# MIDI_Synthesizer.net
KiCad netlist of a schematic drawn in Altium Designer
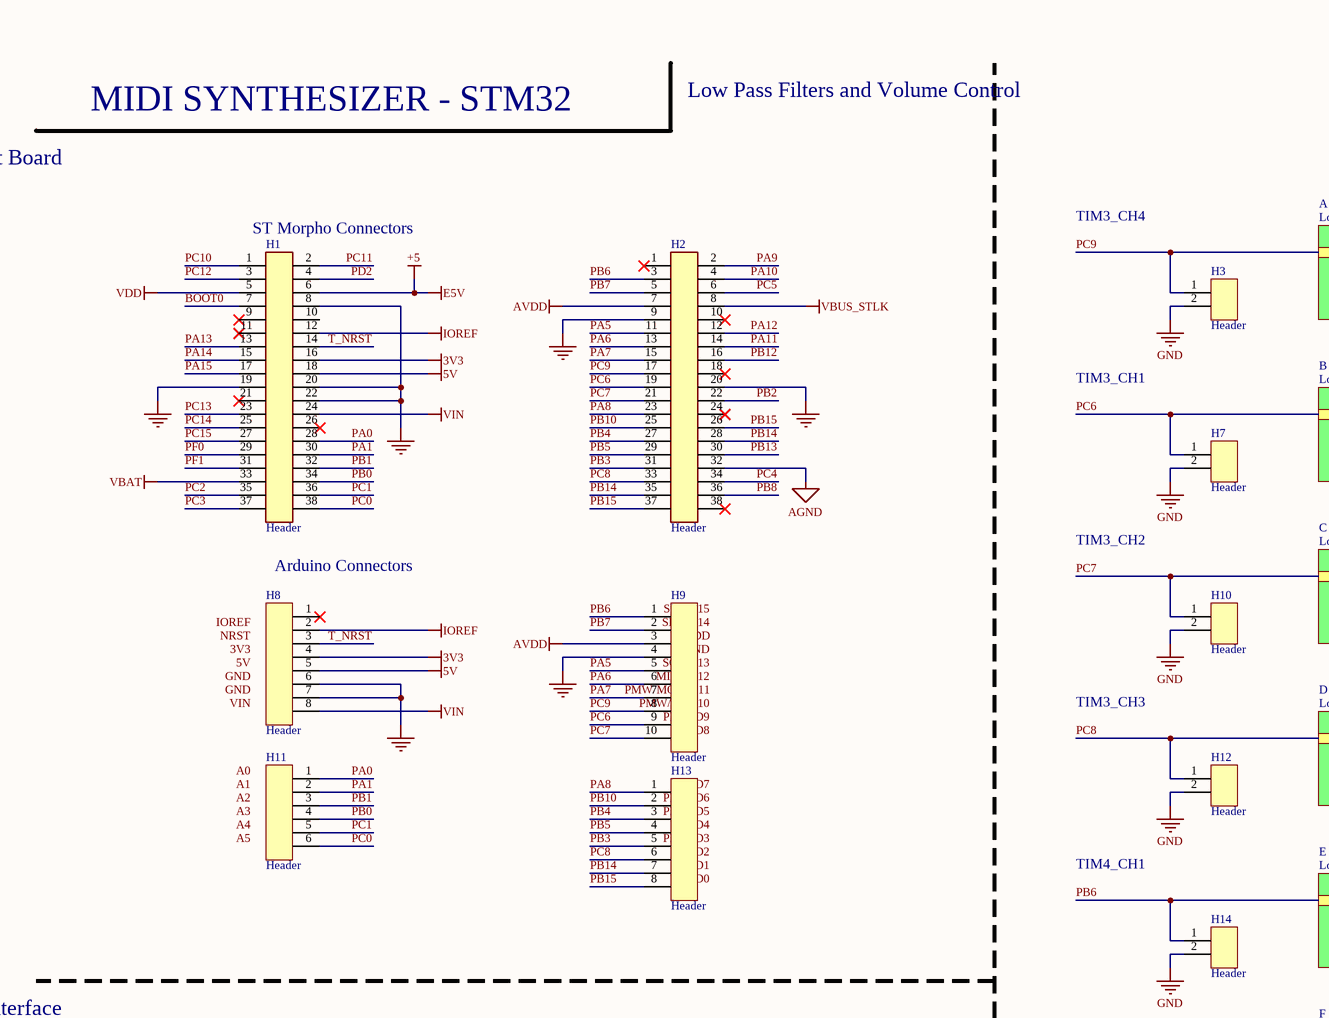
[diagram p0: MIDI_Synthesizer.SchDoc, top left]
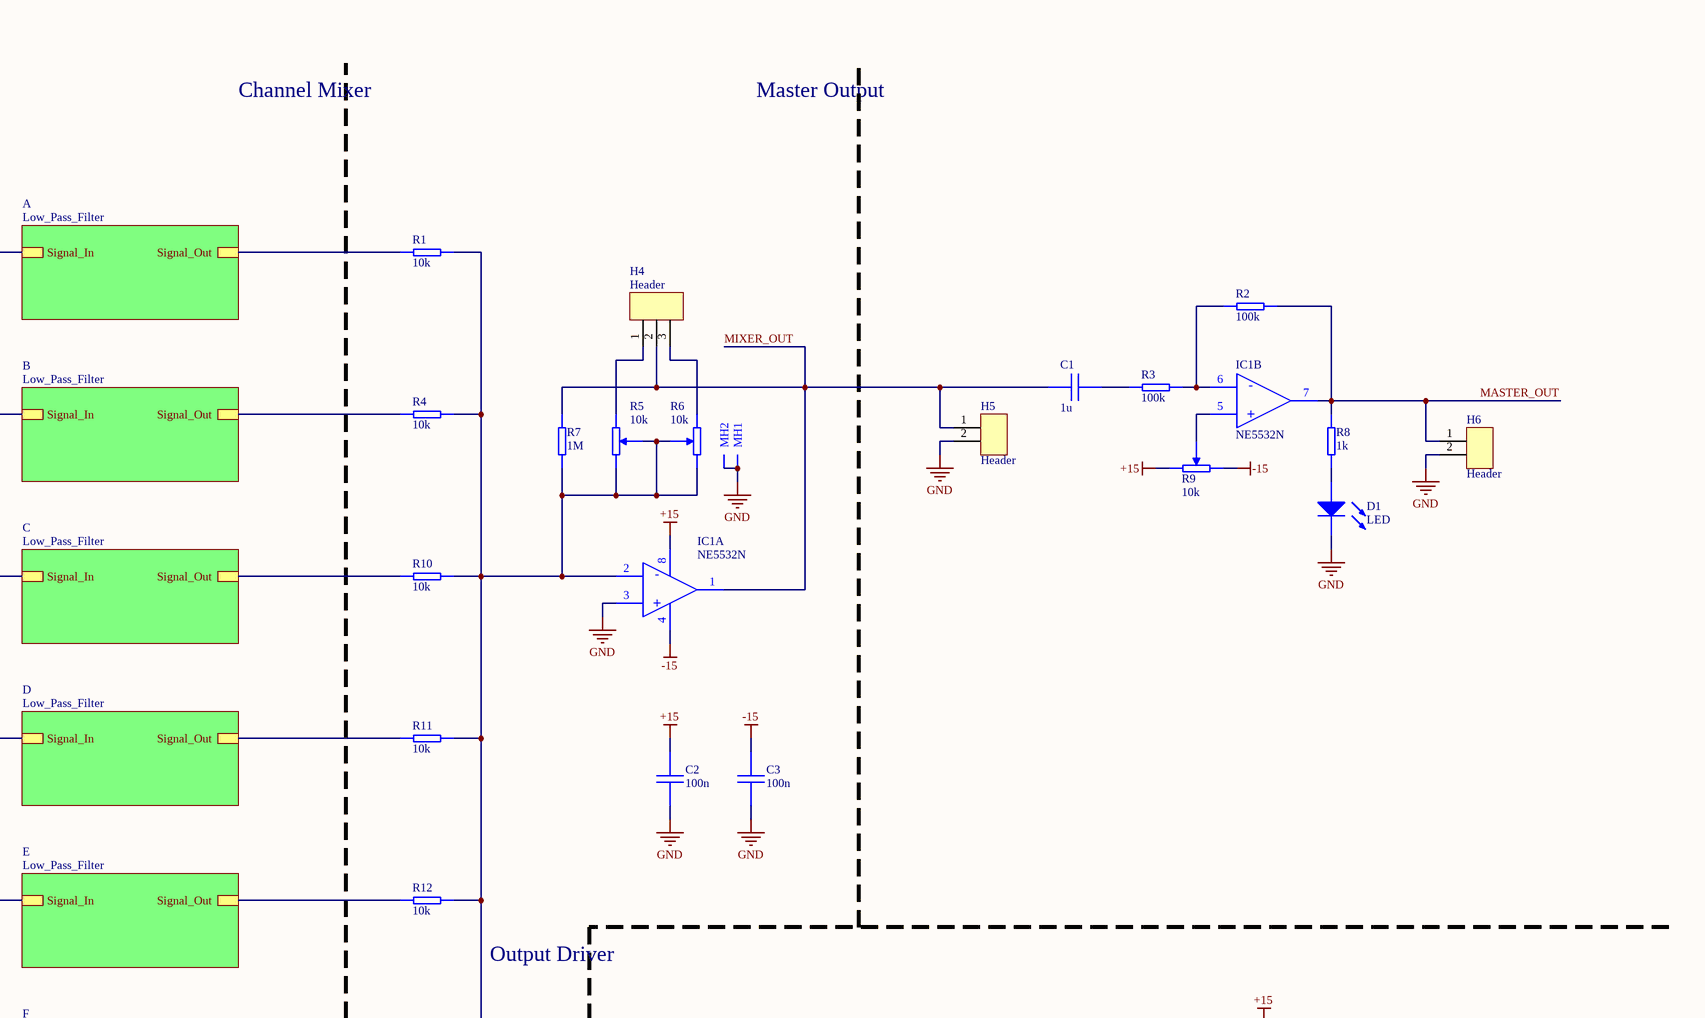
[diagram p1: MIDI_Synthesizer.SchDoc, top right]
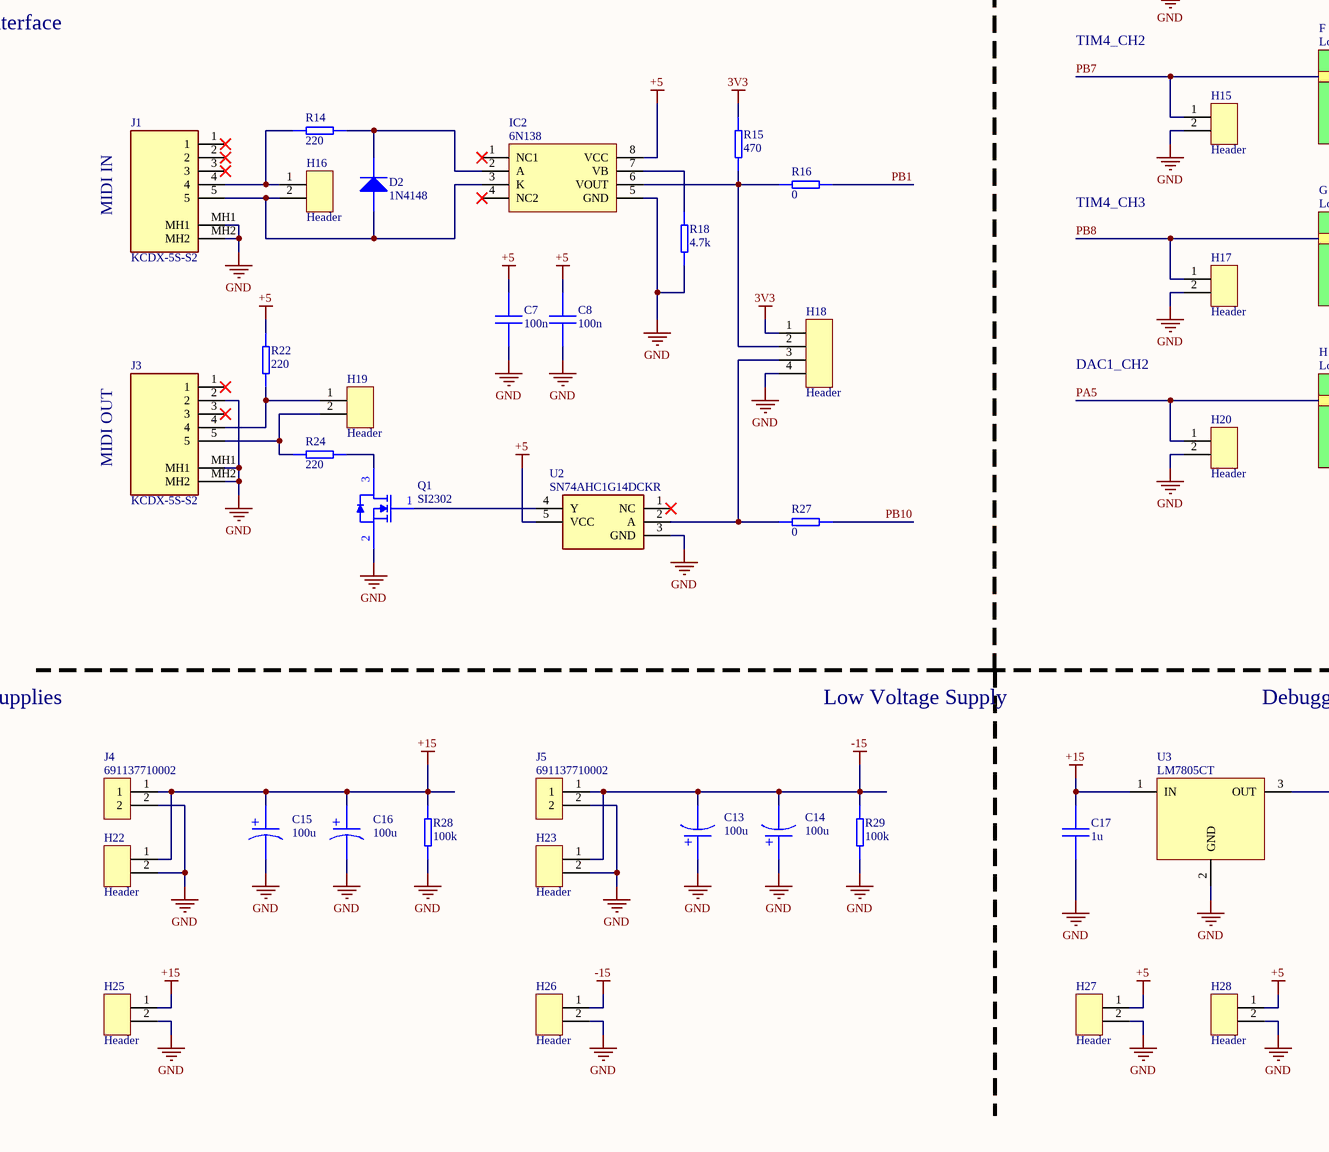
[diagram p2: MIDI_Synthesizer.SchDoc, bottom left]
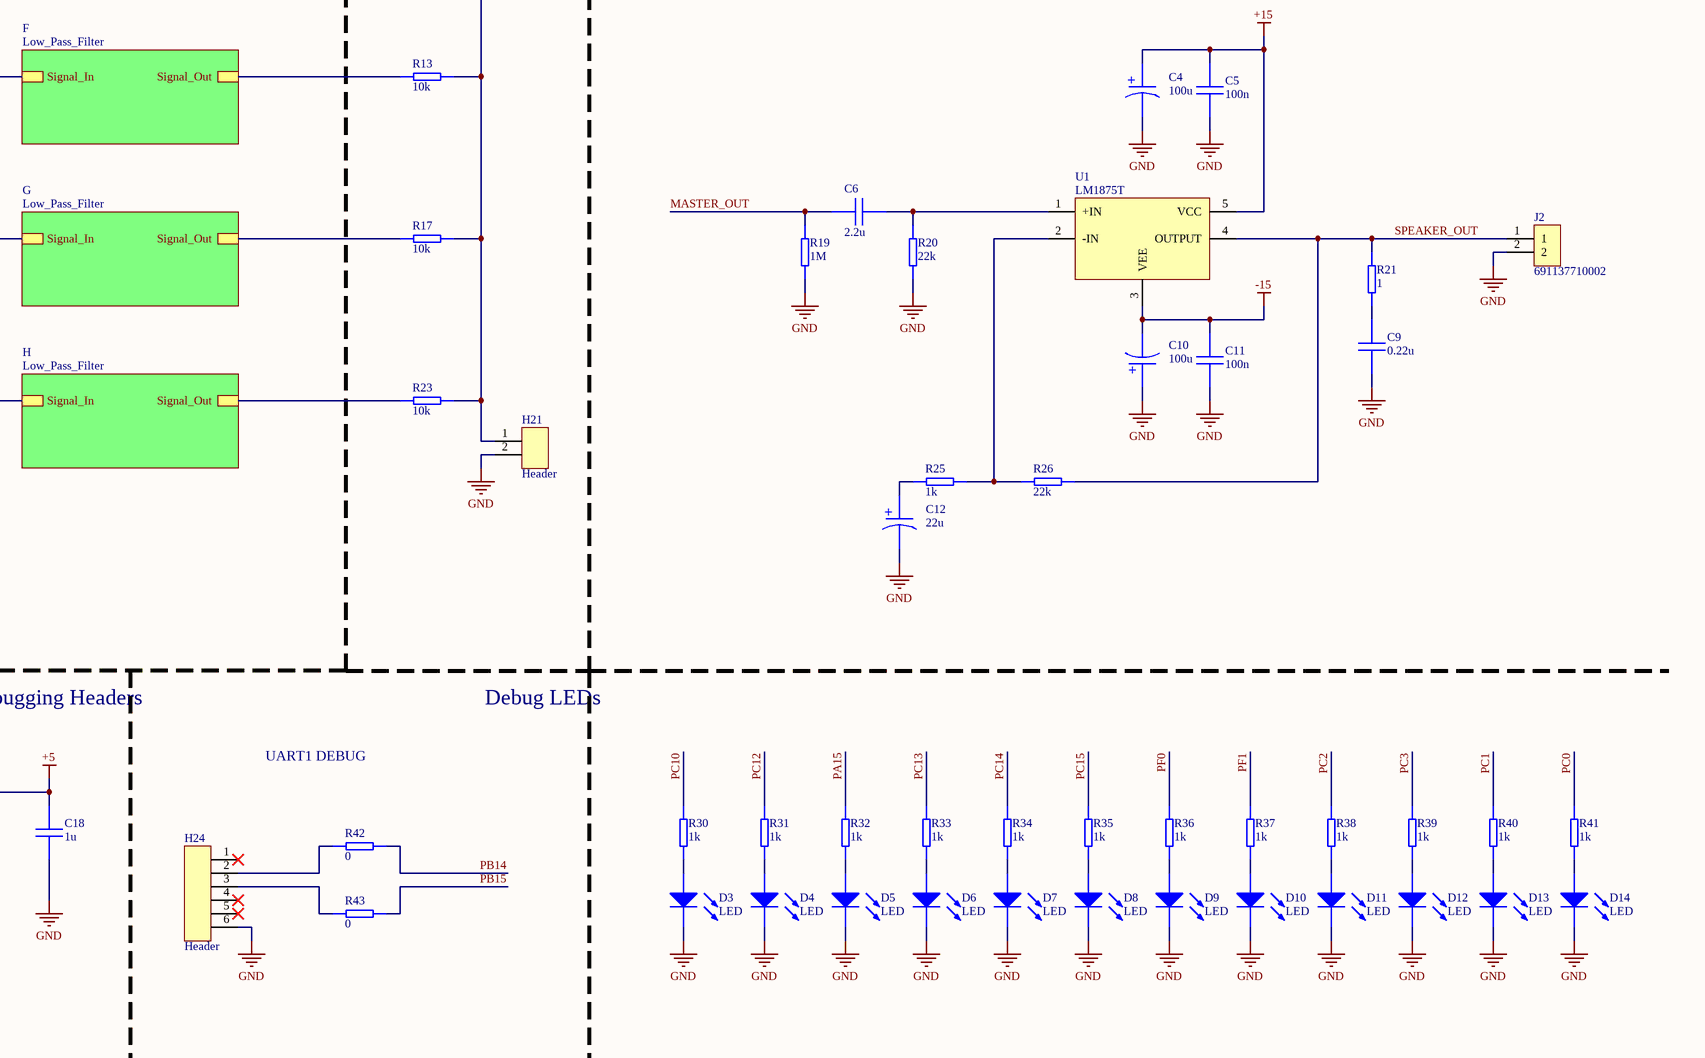
[diagram p3: MIDI_Synthesizer.SchDoc, bottom right]

(export (version "E")
  (design (tool "Eeschema 10.0.6"))
  (components
    (comp (ref "C1")
      (value "1u")
      (footprint "CAP0805")
      (description "Non Polarized Capacitor")
      (libsource (lib "TD") (part "Capacitor - Non Polarized"))
    )
    (comp (ref "C2")
      (value "100n")
      (footprint "CAP0805")
      (description "Non Polarized Capacitor")
      (libsource (lib "TD") (part "Capacitor - Non Polarized"))
    )
    (comp (ref "C3")
      (value "100n")
      (footprint "CAP0805")
      (description "Non Polarized Capacitor")
      (libsource (lib "TD") (part "Capacitor - Non Polarized"))
    )
    (comp (ref "C4")
      (value "100u")
      (footprint "CAPSMD660X800N")
      (description "Polarized Capacitor")
      (libsource (lib "TD") (part "Capacitor - Polarized"))
    )
    (comp (ref "C5")
      (value "100n")
      (footprint "CAP0805")
      (description "Non Polarized Capacitor")
      (libsource (lib "TD") (part "Capacitor - Non Polarized"))
    )
    (comp (ref "C6")
      (value "2.2u")
      (footprint "CAP0805")
      (description "Non Polarized Capacitor")
      (libsource (lib "TD") (part "Capacitor - Non Polarized"))
    )
    (comp (ref "C7")
      (value "100n")
      (footprint "CAP0805")
      (description "Non Polarized Capacitor")
      (libsource (lib "TD") (part "Capacitor - Non Polarized"))
    )
    (comp (ref "C8")
      (value "100n")
      (footprint "CAP0805")
      (description "Non Polarized Capacitor")
      (libsource (lib "TD") (part "Capacitor - Non Polarized"))
    )
    (comp (ref "C9")
      (value "0.22u")
      (footprint "CAP0805")
      (description "Non Polarized Capacitor")
      (libsource (lib "TD") (part "Capacitor - Non Polarized"))
    )
    (comp (ref "C10")
      (value "100u")
      (footprint "CAPSMD660X800N")
      (description "Polarized Capacitor")
      (libsource (lib "") (part "Capacitor - Polarized_1"))
    )
    (comp (ref "C11")
      (value "100n")
      (footprint "CAP0805")
      (description "Non Polarized Capacitor")
      (libsource (lib "TD") (part "Capacitor - Non Polarized"))
    )
    (comp (ref "C12")
      (value "22u")
      (footprint "CAPSMD530X550N")
      (description "Polarized Capacitor")
      (libsource (lib "TD") (part "Capacitor - Polarized"))
    )
    (comp (ref "C13")
      (value "100u")
      (footprint "CAPSMD660X800N")
      (description "Polarized Capacitor")
      (libsource (lib "") (part "Capacitor - Polarized_1"))
    )
    (comp (ref "C14")
      (value "100u")
      (footprint "CAPSMD660X800N")
      (description "Polarized Capacitor")
      (libsource (lib "") (part "Capacitor - Polarized_1"))
    )
    (comp (ref "C15")
      (value "100u")
      (footprint "CAPSMD660X800N")
      (description "Polarized Capacitor")
      (libsource (lib "TD") (part "Capacitor - Polarized"))
    )
    (comp (ref "C16")
      (value "100u")
      (footprint "CAPSMD660X800N")
      (description "Polarized Capacitor")
      (libsource (lib "TD") (part "Capacitor - Polarized"))
    )
    (comp (ref "C17")
      (value "1u")
      (footprint "CAP0805")
      (description "Non Polarized Capacitor")
      (libsource (lib "TD") (part "Capacitor - Non Polarized"))
    )
    (comp (ref "C18")
      (value "1u")
      (footprint "CAP0805")
      (description "Non Polarized Capacitor")
      (libsource (lib "TD") (part "Capacitor - Non Polarized"))
    )
    (comp (ref "D1")
      (value "LED")
      (footprint "LEDM1608X90N")
      (description "General Purpose LED")
      (libsource (lib "TD") (part "LED"))
    )
    (comp (ref "D2")
      (value "1N4148")
      (footprint "SOD123")
      (description "1N4148 General Purpose Switching Diode")
      (libsource (lib "TD") (part "1N4148"))
    )
    (comp (ref "D3")
      (value "LED")
      (footprint "LEDM1608X90N")
      (description "General Purpose LED")
      (libsource (lib "TD") (part "LED"))
    )
    (comp (ref "D4")
      (value "LED")
      (footprint "LEDM1608X90N")
      (description "General Purpose LED")
      (libsource (lib "TD") (part "LED"))
    )
    (comp (ref "D5")
      (value "LED")
      (footprint "LEDM1608X90N")
      (description "General Purpose LED")
      (libsource (lib "TD") (part "LED"))
    )
    (comp (ref "D6")
      (value "LED")
      (footprint "LEDM1608X90N")
      (description "General Purpose LED")
      (libsource (lib "TD") (part "LED"))
    )
    (comp (ref "D7")
      (value "LED")
      (footprint "LEDM1608X90N")
      (description "General Purpose LED")
      (libsource (lib "TD") (part "LED"))
    )
    (comp (ref "D8")
      (value "LED")
      (footprint "LEDM1608X90N")
      (description "General Purpose LED")
      (libsource (lib "TD") (part "LED"))
    )
    (comp (ref "D9")
      (value "LED")
      (footprint "LEDM1608X90N")
      (description "General Purpose LED")
      (libsource (lib "TD") (part "LED"))
    )
    (comp (ref "D10")
      (value "LED")
      (footprint "LEDM1608X90N")
      (description "General Purpose LED")
      (libsource (lib "TD") (part "LED"))
    )
    (comp (ref "D11")
      (value "LED")
      (footprint "LEDM1608X90N")
      (description "General Purpose LED")
      (libsource (lib "TD") (part "LED"))
    )
    (comp (ref "D12")
      (value "LED")
      (footprint "LEDM1608X90N")
      (description "General Purpose LED")
      (libsource (lib "TD") (part "LED"))
    )
    (comp (ref "D13")
      (value "LED")
      (footprint "LEDM1608X90N")
      (description "General Purpose LED")
      (libsource (lib "TD") (part "LED"))
    )
    (comp (ref "D14")
      (value "LED")
      (footprint "LEDM1608X90N")
      (description "General Purpose LED")
      (libsource (lib "TD") (part "LED"))
    )
    (comp (ref "H1")
      (value "Header")
      (footprint "HEADER_2X19")
      (description "38-Pin 2 Row Header")
      (libsource (lib "TD") (part "38-Pin Header (19x2)"))
    )
    (comp (ref "H2")
      (value "Header")
      (footprint "HEADER_2X19")
      (description "38-Pin 2 Row Header")
      (libsource (lib "TD") (part "38-Pin Header (19x2)"))
    )
    (comp (ref "H3")
      (value "Header")
      (footprint "Header_1X2")
      (description "2-Pin Header")
      (libsource (lib "TD") (part "2-Pin Header"))
    )
    (comp (ref "H4")
      (value "Header")
      (footprint "Header_1X3")
      (description "3-Pin Header")
      (libsource (lib "TD") (part "3-Pin Header"))
    )
    (comp (ref "H5")
      (value "Header")
      (footprint "Header_1X2")
      (description "2-Pin Header")
      (libsource (lib "TD") (part "2-Pin Header"))
    )
    (comp (ref "H6")
      (value "Header")
      (footprint "Header_1X2")
      (description "2-Pin Header")
      (libsource (lib "TD") (part "2-Pin Header"))
    )
    (comp (ref "H7")
      (value "Header")
      (footprint "Header_1X2")
      (description "2-Pin Header")
      (libsource (lib "TD") (part "2-Pin Header"))
    )
    (comp (ref "H8")
      (value "Header")
      (footprint "Header_1X8")
      (description "8-Pin Header")
      (libsource (lib "TD") (part "8-Pin Header"))
    )
    (comp (ref "H9")
      (value "Header")
      (footprint "Header_1X10")
      (description "10-Pin Header")
      (libsource (lib "TD") (part "10-Pin Header"))
    )
    (comp (ref "H10")
      (value "Header")
      (footprint "Header_1X2")
      (description "2-Pin Header")
      (libsource (lib "TD") (part "2-Pin Header"))
    )
    (comp (ref "H11")
      (value "Header")
      (footprint "Header_1X6")
      (description "6-Pin Header")
      (libsource (lib "TD") (part "6-Pin Header"))
    )
    (comp (ref "H12")
      (value "Header")
      (footprint "Header_1X2")
      (description "2-Pin Header")
      (libsource (lib "TD") (part "2-Pin Header"))
    )
    (comp (ref "H13")
      (value "Header")
      (footprint "Header_1X8")
      (description "8-Pin Header")
      (libsource (lib "") (part "8-Pin Header_1"))
    )
    (comp (ref "H14")
      (value "Header")
      (footprint "Header_1X2")
      (description "2-Pin Header")
      (libsource (lib "TD") (part "2-Pin Header"))
    )
    (comp (ref "H15")
      (value "Header")
      (footprint "Header_1X2")
      (description "2-Pin Header")
      (libsource (lib "TD") (part "2-Pin Header"))
    )
    (comp (ref "H16")
      (value "Header")
      (footprint "Header_1X2")
      (description "2-Pin Header")
      (libsource (lib "TD") (part "2-Pin Header"))
    )
    (comp (ref "H17")
      (value "Header")
      (footprint "Header_1X2")
      (description "2-Pin Header")
      (libsource (lib "TD") (part "2-Pin Header"))
    )
    (comp (ref "H18")
      (value "Header")
      (footprint "Header_1X4")
      (description "4-Pin Header")
      (libsource (lib "TD") (part "4-Pin Header"))
    )
    (comp (ref "H19")
      (value "Header")
      (footprint "Header_1X2")
      (description "2-Pin Header")
      (libsource (lib "TD") (part "2-Pin Header"))
    )
    (comp (ref "H20")
      (value "Header")
      (footprint "Header_1X2")
      (description "2-Pin Header")
      (libsource (lib "TD") (part "2-Pin Header"))
    )
    (comp (ref "H21")
      (value "Header")
      (footprint "Header_1X2")
      (description "2-Pin Header")
      (libsource (lib "TD") (part "2-Pin Header"))
    )
    (comp (ref "H22")
      (value "Header")
      (footprint "Header_1X2")
      (description "2-Pin Header")
      (libsource (lib "") (part "2-Pin Header_1"))
    )
    (comp (ref "H23")
      (value "Header")
      (footprint "Header_1X2")
      (description "2-Pin Header")
      (libsource (lib "") (part "2-Pin Header_1"))
    )
    (comp (ref "H24")
      (value "Header")
      (footprint "Header_1X6")
      (description "6-Pin Header")
      (libsource (lib "TD") (part "6-Pin Header"))
    )
    (comp (ref "H25")
      (value "Header")
      (footprint "Header_1X2")
      (description "2-Pin Header")
      (libsource (lib "") (part "2-Pin Header_1"))
    )
    (comp (ref "H26")
      (value "Header")
      (footprint "Header_1X2")
      (description "2-Pin Header")
      (libsource (lib "") (part "2-Pin Header_1"))
    )
    (comp (ref "H27")
      (value "Header")
      (footprint "Header_1X2")
      (description "2-Pin Header")
      (libsource (lib "") (part "2-Pin Header_1"))
    )
    (comp (ref "H28")
      (value "Header")
      (footprint "Header_1X2")
      (description "2-Pin Header")
      (libsource (lib "") (part "2-Pin Header_1"))
    )
    (comp (ref "IC1")
      (value "NE5532N")
      (footprint "DIP8")
      (description "Integrated Circuit")
      (fields (field (name "MOUSER PART NUMBER") "863-NE5532N"))
      (libsource (lib "TD") (part "NE5532N"))
    )
    (comp (ref "IC2")
      (value "6N138")
      (footprint "DIP8")
      (description "Integrated Circuit")
      (fields (field (name "MOUSER PART NUMBER") "782-6N138"))
      (libsource (lib "TD") (part "6N138"))
    )
    (comp (ref "J1")
      (value "KCDX-5S-S2")
      (footprint "KCDX5SS2")
      (description "Connector")
      (fields (field (name "MOUSER PART NUMBER") "806-KCDX-5S-S2"))
      (libsource (lib "TD") (part "KCDX-5S-S2"))
    )
    (comp (ref "J2")
      (value "691137710002")
      (footprint "SHDR2W70P0X500_1X2_1000X750X1160P")
      (description "Connector")
      (fields (field (name "MOUSER PART NUMBER") "710-691137710002"))
      (libsource (lib "") (part "691137710002_1"))
    )
    (comp (ref "J3")
      (value "KCDX-5S-S2")
      (footprint "KCDX5SS2")
      (description "Connector")
      (fields (field (name "MOUSER PART NUMBER") "806-KCDX-5S-S2"))
      (libsource (lib "TD") (part "KCDX-5S-S2"))
    )
    (comp (ref "J4")
      (value "691137710002")
      (footprint "SHDR2W70P0X500_1X2_1000X750X1160P")
      (description "Connector")
      (fields (field (name "MOUSER PART NUMBER") "710-691137710002"))
      (libsource (lib "TD") (part "691137710002"))
    )
    (comp (ref "J5")
      (value "691137710002")
      (footprint "SHDR2W70P0X500_1X2_1000X750X1160P")
      (description "Connector")
      (fields (field (name "MOUSER PART NUMBER") "710-691137710002"))
      (libsource (lib "TD") (part "691137710002"))
    )
    (comp (ref "Q1")
      (value "SI2302")
      (footprint "SOT23")
      (description "General Purpose N-Channel MOSFET")
      (libsource (lib "TD_Lib") (part "SI2302"))
    )
    (comp (ref "R1")
      (value "10k")
      (footprint "RESC0805")
      (description "Resistor")
      (libsource (lib "TD") (part "Resistor"))
    )
    (comp (ref "R2")
      (value "100k")
      (footprint "RESC0805")
      (description "Resistor")
      (libsource (lib "TD") (part "Resistor"))
    )
    (comp (ref "R3")
      (value "100k")
      (footprint "RESC0805")
      (description "Resistor")
      (libsource (lib "TD") (part "Resistor"))
    )
    (comp (ref "R4")
      (value "10k")
      (footprint "RESC0805")
      (description "Resistor")
      (libsource (lib "TD") (part "Resistor"))
    )
    (comp (ref "R5")
      (value "10k")
      (footprint "Trim_Pot_Hybrid - No_Silk")
      (description "Potentionmeter")
      (libsource (lib "TD") (part "Potentiometer"))
    )
    (comp (ref "R6")
      (value "10k")
      (footprint "PTV09A4015FB103")
      (description "Potentionmeter")
      (libsource (lib "TD") (part "Potentiometer_Mounted"))
    )
    (comp (ref "R7")
      (value "1M")
      (footprint "RESC0805")
      (description "Resistor")
      (libsource (lib "TD") (part "Resistor"))
    )
    (comp (ref "R8")
      (value "1k")
      (footprint "RESC0805")
      (description "Resistor")
      (libsource (lib "HT2.2") (part "Resistor"))
    )
    (comp (ref "R9")
      (value "10k")
      (footprint "Trim_Pot_Hybrid - No_Silk")
      (description "Potentionmeter")
      (libsource (lib "TD") (part "Potentiometer"))
    )
    (comp (ref "R10")
      (value "10k")
      (footprint "RESC0805")
      (description "Resistor")
      (libsource (lib "TD") (part "Resistor"))
    )
    (comp (ref "R11")
      (value "10k")
      (footprint "RESC0805")
      (description "Resistor")
      (libsource (lib "TD") (part "Resistor"))
    )
    (comp (ref "R12")
      (value "10k")
      (footprint "RESC0805")
      (description "Resistor")
      (libsource (lib "TD") (part "Resistor"))
    )
    (comp (ref "R13")
      (value "10k")
      (footprint "RESC0805")
      (description "Resistor")
      (libsource (lib "TD") (part "Resistor"))
    )
    (comp (ref "R14")
      (value "220")
      (footprint "RESC0805")
      (description "Resistor")
      (libsource (lib "TD") (part "Resistor"))
    )
    (comp (ref "R15")
      (value "470")
      (footprint "RESC0805")
      (description "Resistor")
      (libsource (lib "TD") (part "Resistor"))
    )
    (comp (ref "R16")
      (value "0")
      (footprint "RESC0805")
      (description "Resistor")
      (libsource (lib "TD") (part "Resistor"))
    )
    (comp (ref "R17")
      (value "10k")
      (footprint "RESC0805")
      (description "Resistor")
      (libsource (lib "TD") (part "Resistor"))
    )
    (comp (ref "R18")
      (value "4.7k")
      (footprint "RESC0805")
      (description "Resistor")
      (libsource (lib "TD") (part "Resistor"))
    )
    (comp (ref "R19")
      (value "1M")
      (footprint "RESC0805")
      (description "Resistor")
      (libsource (lib "TD") (part "Resistor"))
    )
    (comp (ref "R20")
      (value "22k")
      (footprint "RESC0805")
      (description "Resistor")
      (libsource (lib "TD") (part "Resistor"))
    )
    (comp (ref "R21")
      (value "1")
      (footprint "RESC0805")
      (description "Resistor")
      (libsource (lib "TD") (part "Resistor"))
    )
    (comp (ref "R22")
      (value "220")
      (footprint "RESC0805")
      (description "Resistor")
      (libsource (lib "TD") (part "Resistor"))
    )
    (comp (ref "R23")
      (value "10k")
      (footprint "RESC0805")
      (description "Resistor")
      (libsource (lib "TD") (part "Resistor"))
    )
    (comp (ref "R24")
      (value "220")
      (footprint "RESC0805")
      (description "Resistor")
      (libsource (lib "TD") (part "Resistor"))
    )
    (comp (ref "R25")
      (value "1k")
      (footprint "RESC0805")
      (description "Resistor")
      (libsource (lib "TD") (part "Resistor"))
    )
    (comp (ref "R26")
      (value "22k")
      (footprint "RESC0805")
      (description "Resistor")
      (libsource (lib "TD") (part "Resistor"))
    )
    (comp (ref "R27")
      (value "0")
      (footprint "RESC0805")
      (description "Resistor")
      (libsource (lib "TD") (part "Resistor"))
    )
    (comp (ref "R28")
      (value "100k")
      (footprint "RESC0805")
      (description "Resistor")
      (libsource (lib "TD") (part "Resistor"))
    )
    (comp (ref "R29")
      (value "100k")
      (footprint "RESC0805")
      (description "Resistor")
      (libsource (lib "TD") (part "Resistor"))
    )
    (comp (ref "R30")
      (value "1k")
      (footprint "RESC0805")
      (description "Resistor")
      (libsource (lib "HT2.2") (part "Resistor"))
    )
    (comp (ref "R31")
      (value "1k")
      (footprint "RESC0805")
      (description "Resistor")
      (libsource (lib "HT2.2") (part "Resistor"))
    )
    (comp (ref "R32")
      (value "1k")
      (footprint "RESC0805")
      (description "Resistor")
      (libsource (lib "HT2.2") (part "Resistor"))
    )
    (comp (ref "R33")
      (value "1k")
      (footprint "RESC0805")
      (description "Resistor")
      (libsource (lib "HT2.2") (part "Resistor"))
    )
    (comp (ref "R34")
      (value "1k")
      (footprint "RESC0805")
      (description "Resistor")
      (libsource (lib "HT2.2") (part "Resistor"))
    )
    (comp (ref "R35")
      (value "1k")
      (footprint "RESC0805")
      (description "Resistor")
      (libsource (lib "HT2.2") (part "Resistor"))
    )
    (comp (ref "R36")
      (value "1k")
      (footprint "RESC0805")
      (description "Resistor")
      (libsource (lib "HT2.2") (part "Resistor"))
    )
    (comp (ref "R37")
      (value "1k")
      (footprint "RESC0805")
      (description "Resistor")
      (libsource (lib "HT2.2") (part "Resistor"))
    )
    (comp (ref "R38")
      (value "1k")
      (footprint "RESC0805")
      (description "Resistor")
      (libsource (lib "HT2.2") (part "Resistor"))
    )
    (comp (ref "R39")
      (value "1k")
      (footprint "RESC0805")
      (description "Resistor")
      (libsource (lib "HT2.2") (part "Resistor"))
    )
    (comp (ref "R40")
      (value "1k")
      (footprint "RESC0805")
      (description "Resistor")
      (libsource (lib "HT2.2") (part "Resistor"))
    )
    (comp (ref "R41")
      (value "1k")
      (footprint "RESC0805")
      (description "Resistor")
      (libsource (lib "HT2.2") (part "Resistor"))
    )
    (comp (ref "R42")
      (value "0")
      (footprint "RESC0805")
      (description "Resistor")
      (libsource (lib "TD") (part "Resistor"))
    )
    (comp (ref "R43")
      (value "0")
      (footprint "RESC0805")
      (description "Resistor")
      (libsource (lib "TD") (part "Resistor"))
    )
    (comp (ref "U1")
      (value "LM1875T")
      (footprint "TO-220-5")
      (description "Integrated Circuit")
      (fields
        (field (name "MANUFACTURER_PART_NUMBER") "LM1875T/NOPB")
        (field (name "MOUSER PART NUMBER") "926-LM1875T/NOPB")
      )
      (libsource (lib "TD") (part "LM1875T"))
    )
    (comp (ref "U2")
      (value "SN74AHC1G14DCKR")
      (footprint "SC70-5")
      (description "Integrated Circuit")
      (fields (field (name "MOUSER PART NUMBER") "595-SN74AHC1G14DCKR"))
      (libsource (lib "TD") (part "SN74AHC1G14DCKR"))
    )
    (comp (ref "U3")
      (value "LM7805CT")
      (footprint "TO-220-3")
      (description "Integrated Circuit")
      (fields (field (name "MOUSER PART NUMBER") "926-LM7805CT"))
      (libsource (lib "TD") (part "LM7805CT"))
    )
  )
  (nets
    (net (code "1") (name "+5") (class "Default")
      (node (ref "C18") (pin "2") (pintype "passive"))
      (node (ref "C7") (pin "2") (pintype "passive"))
      (node (ref "C8") (pin "2") (pintype "passive"))
      (node (ref "H1") (pin "6") (pintype "passive"))
      (node (ref "H27") (pin "1") (pintype "passive"))
      (node (ref "H28") (pin "1") (pintype "passive"))
      (node (ref "IC2") (pin "8") (pinfunction "VCC_8") (pintype "passive"))
      (node (ref "R22") (pin "2") (pintype "passive"))
      (node (ref "U2") (pin "5") (pinfunction "VCC_5") (pintype "passive"))
      (node (ref "U3") (pin "3") (pinfunction "OUT_3") (pintype "passive"))
    )
    (net (code "2") (name "+15") (class "Default")
      (node (ref "C15") (pin "1") (pintype "passive"))
      (node (ref "C16") (pin "1") (pintype "passive"))
      (node (ref "C17") (pin "2") (pintype "passive"))
      (node (ref "C2") (pin "2") (pintype "passive"))
      (node (ref "C4") (pin "1") (pintype "passive"))
      (node (ref "C5") (pin "1") (pintype "passive"))
      (node (ref "H22") (pin "1") (pintype "passive"))
      (node (ref "H25") (pin "1") (pintype "passive"))
      (node (ref "IC1") (pin "8") (pinfunction "V+_8") (pintype "passive"))
      (node (ref "J4") (pin "1") (pinfunction "1_1") (pintype "passive"))
      (node (ref "R28") (pin "1") (pintype "passive"))
      (node (ref "R9") (pin "1") (pintype "passive"))
      (node (ref "U1") (pin "5") (pinfunction "VCC_5") (pintype "passive"))
      (node (ref "U3") (pin "1") (pinfunction "IN_1") (pintype "passive"))
    )
    (net (code "3") (name "-15") (class "Default")
      (node (ref "C10") (pin "2") (pintype "passive"))
      (node (ref "C11") (pin "2") (pintype "passive"))
      (node (ref "C13") (pin "2") (pintype "passive"))
      (node (ref "C14") (pin "2") (pintype "passive"))
      (node (ref "C3") (pin "2") (pintype "passive"))
      (node (ref "H23") (pin "1") (pintype "passive"))
      (node (ref "H26") (pin "1") (pintype "passive"))
      (node (ref "IC1") (pin "4") (pinfunction "V-_4") (pintype "passive"))
      (node (ref "J5") (pin "1") (pinfunction "1_1") (pintype "passive"))
      (node (ref "R29") (pin "1") (pintype "passive"))
      (node (ref "R9") (pin "3") (pintype "passive"))
      (node (ref "U1") (pin "3") (pinfunction "VEE_3") (pintype "passive"))
    )
    (net (code "4") (name "/BOOT0") (class "Default") (node (ref "H1") (pin "7") (pintype "passive")))
    (net (code "5") (name "/MASTER_OUT") (class "Default")
      (node (ref "C6") (pin "2") (pintype "passive"))
      (node (ref "H6") (pin "1") (pintype "passive"))
      (node (ref "IC1") (pin "7") (pinfunction "OUT_B_7") (pintype "passive"))
      (node (ref "R19") (pin "2") (pintype "passive"))
      (node (ref "R2") (pin "1") (pintype "passive"))
      (node (ref "R8") (pin "1") (pintype "passive"))
    )
    (net (code "6") (name "/MIXER_OUT") (class "Default")
      (node (ref "C1") (pin "1") (pintype "passive"))
      (node (ref "H4") (pin "2") (pintype "passive"))
      (node (ref "H5") (pin "1") (pintype "passive"))
      (node (ref "IC1") (pin "1") (pinfunction "OUT_A_1") (pintype "passive"))
      (node (ref "R7") (pin "1") (pintype "passive"))
    )
    (net (code "7") (name "/PA0") (class "Default")
      (node (ref "H1") (pin "28") (pinfunction "28_28") (pintype "passive"))
      (node (ref "H11") (pin "1") (pintype "passive"))
    )
    (net (code "8") (name "/PA1") (class "Default")
      (node (ref "H1") (pin "30") (pinfunction "30_30") (pintype "passive"))
      (node (ref "H11") (pin "2") (pintype "passive"))
    )
    (net (code "9") (name "/PA5") (class "Default")
      (node (ref "H2") (pin "11") (pinfunction "11_11") (pintype "passive"))
      (node (ref "H20") (pin "1") (pintype "passive"))
      (node (ref "H9") (pin "5") (pintype "passive"))
    )
    (net (code "10") (name "/PA6") (class "Default")
      (node (ref "H2") (pin "13") (pinfunction "13_13") (pintype "passive"))
      (node (ref "H9") (pin "6") (pintype "passive"))
    )
    (net (code "11") (name "/PA7") (class "Default")
      (node (ref "H2") (pin "15") (pinfunction "15_15") (pintype "passive"))
      (node (ref "H9") (pin "7") (pintype "passive"))
    )
    (net (code "12") (name "/PA8") (class "Default")
      (node (ref "H13") (pin "1") (pintype "passive"))
      (node (ref "H2") (pin "23") (pinfunction "23_23") (pintype "passive"))
    )
    (net (code "13") (name "/PA9") (class "Default") (node (ref "H2") (pin "2") (pintype "passive")))
    (net (code "14") (name "/PA10") (class "Default") (node (ref "H2") (pin "4") (pintype "passive")))
    (net (code "15") (name "/PA11") (class "Default")
      (node (ref "H2") (pin "14") (pinfunction "14_14") (pintype "passive"))
    )
    (net (code "16") (name "/PA12") (class "Default")
      (node (ref "H2") (pin "12") (pinfunction "12_12") (pintype "passive"))
    )
    (net (code "17") (name "/PA13") (class "Default")
      (node (ref "H1") (pin "13") (pinfunction "13_13") (pintype "passive"))
    )
    (net (code "18") (name "/PA14") (class "Default")
      (node (ref "H1") (pin "15") (pinfunction "15_15") (pintype "passive"))
    )
    (net (code "19") (name "/PA15") (class "Default")
      (node (ref "H1") (pin "17") (pinfunction "17_17") (pintype "passive"))
      (node (ref "R32") (pin "1") (pintype "passive"))
    )
    (net (code "20") (name "/PB0") (class "Default")
      (node (ref "H1") (pin "34") (pinfunction "34_34") (pintype "passive"))
      (node (ref "H11") (pin "4") (pintype "passive"))
    )
    (net (code "21") (name "/PB1") (class "Default")
      (node (ref "H1") (pin "32") (pinfunction "32_32") (pintype "passive"))
      (node (ref "H11") (pin "3") (pintype "passive"))
      (node (ref "R16") (pin "2") (pintype "passive"))
    )
    (net (code "22") (name "/PB2") (class "Default")
      (node (ref "H2") (pin "22") (pinfunction "22_22") (pintype "passive"))
    )
    (net (code "23") (name "/PB3") (class "Default")
      (node (ref "H13") (pin "5") (pintype "passive"))
      (node (ref "H2") (pin "31") (pinfunction "31_31") (pintype "passive"))
    )
    (net (code "24") (name "/PB4") (class "Default")
      (node (ref "H13") (pin "3") (pintype "passive"))
      (node (ref "H2") (pin "27") (pinfunction "27_27") (pintype "passive"))
    )
    (net (code "25") (name "/PB5") (class "Default")
      (node (ref "H13") (pin "4") (pintype "passive"))
      (node (ref "H2") (pin "29") (pinfunction "29_29") (pintype "passive"))
    )
    (net (code "26") (name "/PB6") (class "Default")
      (node (ref "H14") (pin "1") (pintype "passive"))
      (node (ref "H2") (pin "3") (pintype "passive"))
      (node (ref "H9") (pin "1") (pintype "passive"))
    )
    (net (code "27") (name "/PB7") (class "Default")
      (node (ref "H15") (pin "1") (pintype "passive"))
      (node (ref "H2") (pin "5") (pintype "passive"))
      (node (ref "H9") (pin "2") (pintype "passive"))
    )
    (net (code "28") (name "/PB8") (class "Default")
      (node (ref "H17") (pin "1") (pintype "passive"))
      (node (ref "H2") (pin "36") (pinfunction "36_36") (pintype "passive"))
    )
    (net (code "29") (name "/PB10") (class "Default")
      (node (ref "H13") (pin "2") (pintype "passive"))
      (node (ref "H2") (pin "25") (pinfunction "25_25") (pintype "passive"))
      (node (ref "R27") (pin "2") (pintype "passive"))
    )
    (net (code "30") (name "/PB12") (class "Default")
      (node (ref "H2") (pin "16") (pinfunction "16_16") (pintype "passive"))
    )
    (net (code "31") (name "/PB13") (class "Default")
      (node (ref "H2") (pin "30") (pinfunction "30_30") (pintype "passive"))
    )
    (net (code "32") (name "/PB14") (class "Default")
      (node (ref "H13") (pin "7") (pintype "passive"))
      (node (ref "H2") (pin "28") (pinfunction "28_28") (pintype "passive"))
      (node (ref "H2") (pin "35") (pinfunction "35_35") (pintype "passive"))
      (node (ref "R42") (pin "2") (pintype "passive"))
    )
    (net (code "33") (name "/PB15") (class "Default")
      (node (ref "H13") (pin "8") (pintype "passive"))
      (node (ref "H2") (pin "26") (pinfunction "26_26") (pintype "passive"))
      (node (ref "H2") (pin "37") (pinfunction "37_37") (pintype "passive"))
      (node (ref "R43") (pin "2") (pintype "passive"))
    )
    (net (code "34") (name "/PC0") (class "Default")
      (node (ref "H1") (pin "38") (pinfunction "38_38") (pintype "passive"))
      (node (ref "H11") (pin "6") (pintype "passive"))
      (node (ref "R41") (pin "1") (pintype "passive"))
    )
    (net (code "35") (name "/PC1") (class "Default")
      (node (ref "H1") (pin "36") (pinfunction "36_36") (pintype "passive"))
      (node (ref "H11") (pin "5") (pintype "passive"))
      (node (ref "R40") (pin "1") (pintype "passive"))
    )
    (net (code "36") (name "/PC2") (class "Default")
      (node (ref "H1") (pin "35") (pinfunction "35_35") (pintype "passive"))
      (node (ref "R38") (pin "1") (pintype "passive"))
    )
    (net (code "37") (name "/PC3") (class "Default")
      (node (ref "H1") (pin "37") (pinfunction "37_37") (pintype "passive"))
      (node (ref "R39") (pin "1") (pintype "passive"))
    )
    (net (code "38") (name "/PC4") (class "Default")
      (node (ref "H2") (pin "34") (pinfunction "34_34") (pintype "passive"))
    )
    (net (code "39") (name "/PC5") (class "Default") (node (ref "H2") (pin "6") (pintype "passive")))
    (net (code "40") (name "/PC6") (class "Default")
      (node (ref "H2") (pin "19") (pinfunction "19_19") (pintype "passive"))
      (node (ref "H7") (pin "1") (pintype "passive"))
      (node (ref "H9") (pin "9") (pintype "passive"))
    )
    (net (code "41") (name "/PC7") (class "Default")
      (node (ref "H10") (pin "1") (pintype "passive"))
      (node (ref "H2") (pin "21") (pinfunction "21_21") (pintype "passive"))
      (node (ref "H9") (pin "10") (pintype "passive"))
    )
    (net (code "42") (name "/PC8") (class "Default")
      (node (ref "H12") (pin "1") (pintype "passive"))
      (node (ref "H13") (pin "6") (pintype "passive"))
      (node (ref "H2") (pin "33") (pinfunction "33_33") (pintype "passive"))
    )
    (net (code "43") (name "/PC9") (class "Default")
      (node (ref "H2") (pin "17") (pinfunction "17_17") (pintype "passive"))
      (node (ref "H3") (pin "1") (pintype "passive"))
      (node (ref "H9") (pin "8") (pintype "passive"))
    )
    (net (code "44") (name "/PC10") (class "Default")
      (node (ref "H1") (pin "1") (pintype "passive"))
      (node (ref "R30") (pin "1") (pintype "passive"))
    )
    (net (code "45") (name "/PC11") (class "Default") (node (ref "H1") (pin "2") (pintype "passive")))
    (net (code "46") (name "/PC12") (class "Default")
      (node (ref "H1") (pin "3") (pintype "passive"))
      (node (ref "R31") (pin "1") (pintype "passive"))
    )
    (net (code "47") (name "/PC13") (class "Default")
      (node (ref "H1") (pin "23") (pinfunction "23_23") (pintype "passive"))
      (node (ref "R33") (pin "1") (pintype "passive"))
    )
    (net (code "48") (name "/PC14") (class "Default")
      (node (ref "H1") (pin "25") (pinfunction "25_25") (pintype "passive"))
      (node (ref "R34") (pin "1") (pintype "passive"))
    )
    (net (code "49") (name "/PC15") (class "Default")
      (node (ref "H1") (pin "27") (pinfunction "27_27") (pintype "passive"))
      (node (ref "R35") (pin "1") (pintype "passive"))
    )
    (net (code "50") (name "/PD2") (class "Default") (node (ref "H1") (pin "4") (pintype "passive")))
    (net (code "51") (name "/PF0") (class "Default")
      (node (ref "H1") (pin "29") (pinfunction "29_29") (pintype "passive"))
      (node (ref "R36") (pin "1") (pintype "passive"))
    )
    (net (code "52") (name "/PF1") (class "Default")
      (node (ref "H1") (pin "31") (pinfunction "31_31") (pintype "passive"))
      (node (ref "R37") (pin "1") (pintype "passive"))
    )
    (net (code "53") (name "/SPEAKER_OUT") (class "Default")
      (node (ref "J2") (pin "1") (pinfunction "1_1") (pintype "passive"))
      (node (ref "R21") (pin "2") (pintype "passive"))
      (node (ref "R26") (pin "1") (pintype "passive"))
      (node (ref "U1") (pin "4") (pinfunction "OUTPUT_4") (pintype "passive"))
    )
    (net (code "54") (name "/Signal_Out") (class "Default") (node (ref "R1") (pin "1") (pintype "passive")))
    (net (code "55") (name "/Signal_Out_1") (class "Default")
      (node (ref "R12") (pin "1") (pintype "passive"))
    )
    (net (code "56") (name "/Signal_Out_2") (class "Default")
      (node (ref "R13") (pin "1") (pintype "passive"))
    )
    (net (code "57") (name "/Signal_Out_3") (class "Default")
      (node (ref "R17") (pin "1") (pintype "passive"))
    )
    (net (code "58") (name "/Signal_Out_4") (class "Default")
      (node (ref "R23") (pin "1") (pintype "passive"))
    )
    (net (code "59") (name "/Signal_Out_5") (class "Default")
      (node (ref "R10") (pin "1") (pintype "passive"))
    )
    (net (code "60") (name "/Signal_Out_6") (class "Default")
      (node (ref "R11") (pin "1") (pintype "passive"))
    )
    (net (code "61") (name "/Signal_Out_7") (class "Default") (node (ref "R4") (pin "1") (pintype "passive")))
    (net (code "62") (name "/T_NRST") (class "Default")
      (node (ref "H1") (pin "14") (pinfunction "14_14") (pintype "passive"))
      (node (ref "H8") (pin "3") (pintype "passive"))
    )
    (net (code "63") (name "3V3") (class "Default")
      (node (ref "H1") (pin "16") (pinfunction "16_16") (pintype "passive"))
      (node (ref "H18") (pin "1") (pintype "passive"))
      (node (ref "H8") (pin "4") (pintype "passive"))
      (node (ref "R15") (pin "2") (pintype "passive"))
    )
    (net (code "64") (name "5V") (class "Default")
      (node (ref "H1") (pin "18") (pinfunction "18_18") (pintype "passive"))
      (node (ref "H8") (pin "5") (pintype "passive"))
    )
    (net (code "65") (name "AGND") (class "Default")
      (node (ref "H2") (pin "32") (pinfunction "32_32") (pintype "passive"))
    )
    (net (code "66") (name "AVDD") (class "Default")
      (node (ref "H2") (pin "7") (pintype "passive"))
      (node (ref "H9") (pin "3") (pintype "passive"))
    )
    (net (code "67") (name "GND") (class "Default")
      (node (ref "C10") (pin "1") (pintype "passive"))
      (node (ref "C11") (pin "1") (pintype "passive"))
      (node (ref "C12") (pin "2") (pintype "passive"))
      (node (ref "C13") (pin "1") (pintype "passive"))
      (node (ref "C14") (pin "1") (pintype "passive"))
      (node (ref "C15") (pin "2") (pintype "passive"))
      (node (ref "C16") (pin "2") (pintype "passive"))
      (node (ref "C17") (pin "1") (pintype "passive"))
      (node (ref "C18") (pin "1") (pintype "passive"))
      (node (ref "C2") (pin "1") (pintype "passive"))
      (node (ref "C3") (pin "1") (pintype "passive"))
      (node (ref "C4") (pin "2") (pintype "passive"))
      (node (ref "C5") (pin "2") (pintype "passive"))
      (node (ref "C7") (pin "1") (pintype "passive"))
      (node (ref "C8") (pin "1") (pintype "passive"))
      (node (ref "C9") (pin "1") (pintype "passive"))
      (node (ref "D1") (pin "1") (pinfunction "K_1") (pintype "passive"))
      (node (ref "D10") (pin "1") (pinfunction "K_1") (pintype "passive"))
      (node (ref "D11") (pin "1") (pinfunction "K_1") (pintype "passive"))
      (node (ref "D12") (pin "1") (pinfunction "K_1") (pintype "passive"))
      (node (ref "D13") (pin "1") (pinfunction "K_1") (pintype "passive"))
      (node (ref "D14") (pin "1") (pinfunction "K_1") (pintype "passive"))
      (node (ref "D3") (pin "1") (pinfunction "K_1") (pintype "passive"))
      (node (ref "D4") (pin "1") (pinfunction "K_1") (pintype "passive"))
      (node (ref "D5") (pin "1") (pinfunction "K_1") (pintype "passive"))
      (node (ref "D6") (pin "1") (pinfunction "K_1") (pintype "passive"))
      (node (ref "D7") (pin "1") (pinfunction "K_1") (pintype "passive"))
      (node (ref "D8") (pin "1") (pinfunction "K_1") (pintype "passive"))
      (node (ref "D9") (pin "1") (pinfunction "K_1") (pintype "passive"))
      (node (ref "H1") (pin "19") (pinfunction "19_19") (pintype "passive"))
      (node (ref "H1") (pin "20") (pinfunction "20_20") (pintype "passive"))
      (node (ref "H1") (pin "22") (pinfunction "22_22") (pintype "passive"))
      (node (ref "H1") (pin "8") (pintype "passive"))
      (node (ref "H10") (pin "2") (pintype "passive"))
      (node (ref "H12") (pin "2") (pintype "passive"))
      (node (ref "H14") (pin "2") (pintype "passive"))
      (node (ref "H15") (pin "2") (pintype "passive"))
      (node (ref "H17") (pin "2") (pintype "passive"))
      (node (ref "H18") (pin "4") (pintype "passive"))
      (node (ref "H2") (pin "20") (pinfunction "20_20") (pintype "passive"))
      (node (ref "H2") (pin "9") (pinfunction "9_9") (pintype "passive"))
      (node (ref "H20") (pin "2") (pintype "passive"))
      (node (ref "H21") (pin "2") (pintype "passive"))
      (node (ref "H22") (pin "2") (pintype "passive"))
      (node (ref "H23") (pin "2") (pintype "passive"))
      (node (ref "H24") (pin "6") (pintype "passive"))
      (node (ref "H25") (pin "2") (pintype "passive"))
      (node (ref "H26") (pin "2") (pintype "passive"))
      (node (ref "H27") (pin "2") (pintype "passive"))
      (node (ref "H28") (pin "2") (pintype "passive"))
      (node (ref "H3") (pin "2") (pintype "passive"))
      (node (ref "H5") (pin "2") (pintype "passive"))
      (node (ref "H6") (pin "2") (pintype "passive"))
      (node (ref "H7") (pin "2") (pintype "passive"))
      (node (ref "H8") (pin "6") (pintype "passive"))
      (node (ref "H8") (pin "7") (pintype "passive"))
      (node (ref "H9") (pin "4") (pintype "passive"))
      (node (ref "IC1") (pin "3") (pinfunction "+IN_A_3") (pintype "passive"))
      (node (ref "IC2") (pin "5") (pinfunction "GND_5") (pintype "passive"))
      (node (ref "J1") (pin "MH1") (pinfunction "MH1_MH1") (pintype "passive"))
      (node (ref "J1") (pin "MH2") (pinfunction "MH2_MH2") (pintype "passive"))
      (node (ref "J2") (pin "2") (pinfunction "2_2") (pintype "passive"))
      (node (ref "J3") (pin "2") (pinfunction "2_2") (pintype "passive"))
      (node (ref "J3") (pin "MH1") (pinfunction "MH1_MH1") (pintype "passive"))
      (node (ref "J3") (pin "MH2") (pinfunction "MH2_MH2") (pintype "passive"))
      (node (ref "J4") (pin "2") (pinfunction "2_2") (pintype "passive"))
      (node (ref "J5") (pin "2") (pinfunction "2_2") (pintype "passive"))
      (node (ref "Q1") (pin "2") (pinfunction "S_2") (pintype "passive"))
      (node (ref "R18") (pin "1") (pintype "passive"))
      (node (ref "R19") (pin "1") (pintype "passive"))
      (node (ref "R20") (pin "1") (pintype "passive"))
      (node (ref "R28") (pin "2") (pintype "passive"))
      (node (ref "R29") (pin "2") (pintype "passive"))
      (node (ref "R6") (pin "4") (pinfunction "MH1_4") (pintype "passive"))
      (node (ref "R6") (pin "5") (pinfunction "MH2_5") (pintype "passive"))
      (node (ref "U2") (pin "3") (pinfunction "GND_3") (pintype "passive"))
      (node (ref "U3") (pin "2") (pinfunction "GND_2") (pintype "passive"))
    )
    (net (code "68") (name "IOREF") (class "Default")
      (node (ref "H1") (pin "12") (pinfunction "12_12") (pintype "passive"))
      (node (ref "H8") (pin "2") (pintype "passive"))
    )
    (net (code "69") (name "Net-(C1-Pad2)") (class "Default")
      (node (ref "C1") (pin "2") (pintype "passive"))
      (node (ref "R3") (pin "2") (pintype "passive"))
    )
    (net (code "70") (name "Net-(C9-Pad2)") (class "Default")
      (node (ref "C9") (pin "2") (pintype "passive"))
      (node (ref "R21") (pin "1") (pintype "passive"))
    )
    (net (code "71") (name "Net-(C12-Pad1)") (class "Default")
      (node (ref "C12") (pin "1") (pintype "passive"))
      (node (ref "R25") (pin "1") (pintype "passive"))
    )
    (net (code "72") (name "Net-(D1-A)") (class "Default")
      (node (ref "D1") (pin "2") (pinfunction "A_2") (pintype "passive"))
      (node (ref "R8") (pin "2") (pintype "passive"))
    )
    (net (code "73") (name "Net-(D2-A)") (class "Default")
      (node (ref "D2") (pin "2") (pinfunction "A_2") (pintype "passive"))
      (node (ref "H16") (pin "2") (pintype "passive"))
      (node (ref "IC2") (pin "3") (pinfunction "K_3") (pintype "passive"))
      (node (ref "J1") (pin "5") (pinfunction "5_5") (pintype "passive"))
    )
    (net (code "74") (name "Net-(D2-K)") (class "Default")
      (node (ref "D2") (pin "1") (pinfunction "K_1") (pintype "passive"))
      (node (ref "IC2") (pin "2") (pinfunction "A_2") (pintype "passive"))
      (node (ref "R14") (pin "2") (pintype "passive"))
    )
    (net (code "75") (name "Net-(D3-A)") (class "Default")
      (node (ref "D3") (pin "2") (pinfunction "A_2") (pintype "passive"))
      (node (ref "R30") (pin "2") (pintype "passive"))
    )
    (net (code "76") (name "Net-(D4-A)") (class "Default")
      (node (ref "D4") (pin "2") (pinfunction "A_2") (pintype "passive"))
      (node (ref "R31") (pin "2") (pintype "passive"))
    )
    (net (code "77") (name "Net-(D5-A)") (class "Default")
      (node (ref "D5") (pin "2") (pinfunction "A_2") (pintype "passive"))
      (node (ref "R32") (pin "2") (pintype "passive"))
    )
    (net (code "78") (name "Net-(D6-A)") (class "Default")
      (node (ref "D6") (pin "2") (pinfunction "A_2") (pintype "passive"))
      (node (ref "R33") (pin "2") (pintype "passive"))
    )
    (net (code "79") (name "Net-(D7-A)") (class "Default")
      (node (ref "D7") (pin "2") (pinfunction "A_2") (pintype "passive"))
      (node (ref "R34") (pin "2") (pintype "passive"))
    )
    (net (code "80") (name "Net-(D8-A)") (class "Default")
      (node (ref "D8") (pin "2") (pinfunction "A_2") (pintype "passive"))
      (node (ref "R35") (pin "2") (pintype "passive"))
    )
    (net (code "81") (name "Net-(D9-A)") (class "Default")
      (node (ref "D9") (pin "2") (pinfunction "A_2") (pintype "passive"))
      (node (ref "R36") (pin "2") (pintype "passive"))
    )
    (net (code "82") (name "Net-(D10-A)") (class "Default")
      (node (ref "D10") (pin "2") (pinfunction "A_2") (pintype "passive"))
      (node (ref "R37") (pin "2") (pintype "passive"))
    )
    (net (code "83") (name "Net-(D11-A)") (class "Default")
      (node (ref "D11") (pin "2") (pinfunction "A_2") (pintype "passive"))
      (node (ref "R38") (pin "2") (pintype "passive"))
    )
    (net (code "84") (name "Net-(D12-A)") (class "Default")
      (node (ref "D12") (pin "2") (pinfunction "A_2") (pintype "passive"))
      (node (ref "R39") (pin "2") (pintype "passive"))
    )
    (net (code "85") (name "Net-(D13-A)") (class "Default")
      (node (ref "D13") (pin "2") (pinfunction "A_2") (pintype "passive"))
      (node (ref "R40") (pin "2") (pintype "passive"))
    )
    (net (code "86") (name "Net-(D14-A)") (class "Default")
      (node (ref "D14") (pin "2") (pinfunction "A_2") (pintype "passive"))
      (node (ref "R41") (pin "2") (pintype "passive"))
    )
    (net (code "87") (name "Net-(H4-Pad1)") (class "Default")
      (node (ref "H4") (pin "1") (pintype "passive"))
      (node (ref "R5") (pin "1") (pintype "passive"))
    )
    (net (code "88") (name "Net-(H4-Pad3)") (class "Default")
      (node (ref "H4") (pin "3") (pintype "passive"))
      (node (ref "R6") (pin "1") (pintype "passive"))
    )
    (net (code "89") (name "Net-(H16-Pad1)") (class "Default")
      (node (ref "H16") (pin "1") (pintype "passive"))
      (node (ref "J1") (pin "4") (pinfunction "4_4") (pintype "passive"))
      (node (ref "R14") (pin "1") (pintype "passive"))
    )
    (net (code "90") (name "Net-(H19-Pad1)") (class "Default")
      (node (ref "H19") (pin "1") (pintype "passive"))
      (node (ref "J3") (pin "4") (pinfunction "4_4") (pintype "passive"))
      (node (ref "R22") (pin "1") (pintype "passive"))
    )
    (net (code "91") (name "Net-(H19-Pad2)") (class "Default")
      (node (ref "H19") (pin "2") (pintype "passive"))
      (node (ref "J3") (pin "5") (pinfunction "5_5") (pintype "passive"))
      (node (ref "R24") (pin "2") (pintype "passive"))
    )
    (net (code "92") (name "Net-(H24-Pad2)") (class "Default")
      (node (ref "H24") (pin "2") (pintype "passive"))
      (node (ref "R42") (pin "1") (pintype "passive"))
    )
    (net (code "93") (name "Net-(H24-Pad3)") (class "Default")
      (node (ref "H24") (pin "3") (pintype "passive"))
      (node (ref "R43") (pin "1") (pintype "passive"))
    )
    (net (code "94") (name "Net-(IC1A--IN_A)") (class "Default")
      (node (ref "H21") (pin "1") (pintype "passive"))
      (node (ref "IC1") (pin "2") (pinfunction "-IN_A_2") (pintype "passive"))
      (node (ref "R1") (pin "2") (pintype "passive"))
      (node (ref "R10") (pin "2") (pintype "passive"))
      (node (ref "R11") (pin "2") (pintype "passive"))
      (node (ref "R12") (pin "2") (pintype "passive"))
      (node (ref "R13") (pin "2") (pintype "passive"))
      (node (ref "R17") (pin "2") (pintype "passive"))
      (node (ref "R23") (pin "2") (pintype "passive"))
      (node (ref "R4") (pin "2") (pintype "passive"))
      (node (ref "R5") (pin "2") (pintype "passive"))
      (node (ref "R5") (pin "3") (pintype "passive"))
      (node (ref "R6") (pin "2") (pintype "passive"))
      (node (ref "R6") (pin "3") (pintype "passive"))
      (node (ref "R7") (pin "2") (pintype "passive"))
    )
    (net (code "95") (name "Net-(IC1B-+IN_B)") (class "Default")
      (node (ref "IC1") (pin "5") (pinfunction "+IN_B_5") (pintype "passive"))
      (node (ref "R9") (pin "2") (pintype "passive"))
    )
    (net (code "96") (name "Net-(IC1B--IN_B)") (class "Default")
      (node (ref "IC1") (pin "6") (pinfunction "-IN_B_6") (pintype "passive"))
      (node (ref "R2") (pin "2") (pintype "passive"))
      (node (ref "R3") (pin "1") (pintype "passive"))
    )
    (net (code "97") (name "Net-(IC2-VB)") (class "Default")
      (node (ref "IC2") (pin "7") (pinfunction "VB_7") (pintype "passive"))
      (node (ref "R18") (pin "2") (pintype "passive"))
    )
    (net (code "98") (name "Net-(IC2-VOUT)") (class "Default")
      (node (ref "H18") (pin "2") (pintype "passive"))
      (node (ref "IC2") (pin "6") (pinfunction "VOUT_6") (pintype "passive"))
      (node (ref "R15") (pin "1") (pintype "passive"))
      (node (ref "R16") (pin "1") (pintype "passive"))
    )
    (net (code "99") (name "Net-(Q1-D)") (class "Default")
      (node (ref "Q1") (pin "3") (pinfunction "D_3") (pintype "passive"))
      (node (ref "R24") (pin "1") (pintype "passive"))
    )
    (net (code "100") (name "Net-(Q1-G)") (class "Default")
      (node (ref "Q1") (pin "1") (pinfunction "G_1") (pintype "passive"))
      (node (ref "U2") (pin "4") (pinfunction "Y_4") (pintype "passive"))
    )
    (net (code "101") (name "Net-(U1-+IN)") (class "Default")
      (node (ref "C6") (pin "1") (pintype "passive"))
      (node (ref "R20") (pin "2") (pintype "passive"))
      (node (ref "U1") (pin "1") (pinfunction "+IN_1") (pintype "passive"))
    )
    (net (code "102") (name "Net-(U1--IN)") (class "Default")
      (node (ref "R25") (pin "2") (pintype "passive"))
      (node (ref "R26") (pin "2") (pintype "passive"))
      (node (ref "U1") (pin "2") (pinfunction "-IN_2") (pintype "passive"))
    )
    (net (code "103") (name "Net-(U2-A)") (class "Default")
      (node (ref "H18") (pin "3") (pintype "passive"))
      (node (ref "R27") (pin "1") (pintype "passive"))
      (node (ref "U2") (pin "2") (pinfunction "A_2") (pintype "passive"))
    )
    (net (code "104") (name "VBAT") (class "Default")
      (node (ref "H1") (pin "33") (pinfunction "33_33") (pintype "passive"))
    )
    (net (code "105") (name "VBUS_STLK") (class "Default") (node (ref "H2") (pin "8") (pintype "passive")))
    (net (code "106") (name "VDD") (class "Default") (node (ref "H1") (pin "5") (pintype "passive")))
    (net (code "107") (name "VIN") (class "Default")
      (node (ref "H1") (pin "24") (pinfunction "24_24") (pintype "passive"))
      (node (ref "H8") (pin "8") (pintype "passive"))
    )
    (net (code "108") (name "unconnected-(H1-Pad9)") (class "Default")
      (node (ref "H1") (pin "9") (pinfunction "9_9") (pintype "passive+no_connect"))
    )
    (net (code "109") (name "unconnected-(H1-Pad10)") (class "Default")
      (node (ref "H1") (pin "10") (pinfunction "10_10") (pintype "passive"))
    )
    (net (code "110") (name "unconnected-(H1-Pad11)") (class "Default")
      (node (ref "H1") (pin "11") (pinfunction "11_11") (pintype "passive+no_connect"))
    )
    (net (code "111") (name "unconnected-(H1-Pad21)") (class "Default")
      (node (ref "H1") (pin "21") (pinfunction "21_21") (pintype "passive+no_connect"))
    )
    (net (code "112") (name "unconnected-(H1-Pad26)") (class "Default")
      (node (ref "H1") (pin "26") (pinfunction "26_26") (pintype "passive+no_connect"))
    )
    (net (code "113") (name "unconnected-(H2-Pad1)") (class "Default")
      (node (ref "H2") (pin "1") (pintype "passive+no_connect"))
    )
    (net (code "114") (name "unconnected-(H2-Pad10)") (class "Default")
      (node (ref "H2") (pin "10") (pinfunction "10_10") (pintype "passive+no_connect"))
    )
    (net (code "115") (name "unconnected-(H2-Pad18)") (class "Default")
      (node (ref "H2") (pin "18") (pinfunction "18_18") (pintype "passive+no_connect"))
    )
    (net (code "116") (name "unconnected-(H2-Pad24)") (class "Default")
      (node (ref "H2") (pin "24") (pinfunction "24_24") (pintype "passive+no_connect"))
    )
    (net (code "117") (name "unconnected-(H2-Pad38)") (class "Default")
      (node (ref "H2") (pin "38") (pinfunction "38_38") (pintype "passive+no_connect"))
    )
    (net (code "118") (name "unconnected-(H8-Pad1)") (class "Default")
      (node (ref "H8") (pin "1") (pintype "passive+no_connect"))
    )
    (net (code "119") (name "unconnected-(H24-Pad1)") (class "Default")
      (node (ref "H24") (pin "1") (pintype "passive+no_connect"))
    )
    (net (code "120") (name "unconnected-(H24-Pad4)") (class "Default")
      (node (ref "H24") (pin "4") (pintype "passive+no_connect"))
    )
    (net (code "121") (name "unconnected-(H24-Pad5)") (class "Default")
      (node (ref "H24") (pin "5") (pintype "passive+no_connect"))
    )
    (net (code "122") (name "unconnected-(IC2-NC1-Pad1)") (class "Default")
      (node (ref "IC2") (pin "1") (pinfunction "NC1_1") (pintype "passive+no_connect"))
    )
    (net (code "123") (name "unconnected-(IC2-NC2-Pad4)") (class "Default")
      (node (ref "IC2") (pin "4") (pinfunction "NC2_4") (pintype "passive+no_connect"))
    )
    (net (code "124") (name "unconnected-(J1-Pad1)") (class "Default")
      (node (ref "J1") (pin "1") (pinfunction "1_1") (pintype "passive+no_connect"))
    )
    (net (code "125") (name "unconnected-(J1-Pad2)") (class "Default")
      (node (ref "J1") (pin "2") (pinfunction "2_2") (pintype "passive+no_connect"))
    )
    (net (code "126") (name "unconnected-(J1-Pad3)") (class "Default")
      (node (ref "J1") (pin "3") (pinfunction "3_3") (pintype "passive+no_connect"))
    )
    (net (code "127") (name "unconnected-(J3-Pad1)") (class "Default")
      (node (ref "J3") (pin "1") (pinfunction "1_1") (pintype "passive+no_connect"))
    )
    (net (code "128") (name "unconnected-(J3-Pad3)") (class "Default")
      (node (ref "J3") (pin "3") (pinfunction "3_3") (pintype "passive+no_connect"))
    )
    (net (code "129") (name "unconnected-(U2-NC-Pad1)") (class "Default")
      (node (ref "U2") (pin "1") (pinfunction "NC_1") (pintype "passive+no_connect"))
    )
  )
)
